# SpiSlvWiring.net
KiCad netlist of a schematic drawn in EAGLE
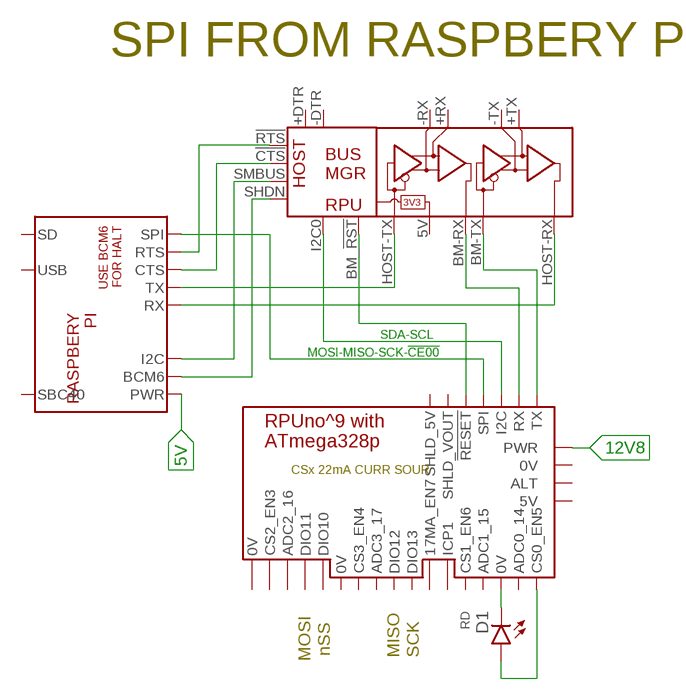
[diagram p0: schematic, sheet 1]

(export (version "E")
  (design (tool "Eeschema 10.0.6"))
  (components
    (comp (ref "BM1")
      (value "RPUNO")
      (footprint "eagle-import:NA-30")
      (libsource (lib "eagle-import") (part "RPUNO"))
    )
    (comp (ref "D1")
      (value "RD")
      (footprint "eagle-import:LED5MM")
      (libsource (lib "eagle-import") (part "LED5MM"))
    )
    (comp (ref "U$1")
      (value "PI")
      (footprint "eagle-import:NA-30")
      (libsource (lib "eagle-import") (part "PI"))
    )
    (comp (ref "U$2")
      (value "BUS_MGR")
      (footprint "eagle-import:WITH_RPU_NAMES")
      (libsource (lib "eagle-import") (part "BUS_MGR"))
    )
  )
  (nets
    (net (code "1") (name "/MOSI-MISO-SCK-~{CE00}") (class "Default")
      (node (ref "BM1") (pin "4") (pinfunction "SPI_4") (pintype "bidirectional"))
      (node (ref "U$1") (pin "10") (pinfunction "SPI_10") (pintype "bidirectional"))
    )
    (net (code "2") (name "/SDA-SCL") (class "Default")
      (node (ref "BM1") (pin "3") (pinfunction "I2C_3") (pintype "bidirectional"))
      (node (ref "U$2") (pin "I2C0") (pinfunction "I2C0_I2C0") (pintype "bidirectional"))
    )
    (net (code "3") (name "5V") (class "Default")
      (node (ref "U$1") (pin "12") (pinfunction "PWR_12") (pintype "bidirectional"))
    )
    (net (code "4") (name "12V8") (class "Default")
      (node (ref "BM1") (pin "8") (pinfunction "PWR_8") (pintype "bidirectional"))
    )
    (net (code "5") (name "Net-(BM1-0V-Pad26)") (class "Default")
      (node (ref "BM1") (pin "26") (pinfunction "0V_26") (pintype "bidirectional"))
      (node (ref "D1") (pin "K") (pinfunction "K_K") (pintype "passive"))
    )
    (net (code "6") (name "Net-(BM1-CS0_EN5)") (class "Default")
      (node (ref "BM1") (pin "23") (pinfunction "CS0_EN5_23") (pintype "bidirectional"))
      (node (ref "D1") (pin "A") (pinfunction "A_A") (pintype "passive"))
    )
    (net (code "7") (name "Net-(BM1-RX)") (class "Default")
      (node (ref "BM1") (pin "2") (pinfunction "RX_2") (pintype "bidirectional"))
      (node (ref "U$2") (pin "BM-RX") (pinfunction "BM_RX_BM-RX") (pintype "bidirectional"))
    )
    (net (code "8") (name "Net-(BM1-TX)") (class "Default")
      (node (ref "BM1") (pin "1") (pinfunction "TX_1") (pintype "bidirectional"))
      (node (ref "U$2") (pin "BM-TX") (pinfunction "BM_TX_BM-TX") (pintype "bidirectional"))
    )
    (net (code "9") (name "Net-(BM1-~{RESET})") (class "Default")
      (node (ref "BM1") (pin "5") (pinfunction "~{RESET}_5") (pintype "bidirectional"))
      (node (ref "U$2") (pin "BM_!RST!") (pinfunction "BM-~{RST}_BM_!RST!") (pintype "bidirectional"))
    )
    (net (code "10") (name "Net-(U$1-BCM6)") (class "Default")
      (node (ref "U$1") (pin "7") (pinfunction "BCM6_7") (pintype "bidirectional"))
      (node (ref "U$2") (pin "SHDN") (pinfunction "SHDN_SHDN") (pintype "bidirectional"))
    )
    (net (code "11") (name "Net-(U$1-CTS)") (class "Default")
      (node (ref "U$1") (pin "1") (pinfunction "CTS_1") (pintype "input"))
      (node (ref "U$2") (pin "!CTS") (pinfunction "~{CTS}_!CTS") (pintype "bidirectional"))
    )
    (net (code "12") (name "Net-(U$1-I2C)") (class "Default")
      (node (ref "U$1") (pin "8") (pinfunction "I2C_8") (pintype "bidirectional"))
      (node (ref "U$2") (pin "SMBUS") (pinfunction "SMBUS_SMBUS") (pintype "bidirectional"))
    )
    (net (code "13") (name "Net-(U$1-RTS)") (class "Default")
      (node (ref "U$1") (pin "2") (pinfunction "RTS_2") (pintype "input"))
      (node (ref "U$2") (pin "!RTS") (pinfunction "~{RTS}_!RTS") (pintype "bidirectional"))
    )
    (net (code "14") (name "Net-(U$1-RX)") (class "Default")
      (node (ref "U$1") (pin "3") (pinfunction "RX_3") (pintype "bidirectional"))
      (node (ref "U$2") (pin "HOST-RX") (pinfunction "HOST_RX_HOST-RX") (pintype "bidirectional"))
    )
    (net (code "15") (name "Net-(U$1-TX)") (class "Default")
      (node (ref "U$1") (pin "4") (pinfunction "TX_4") (pintype "bidirectional"))
      (node (ref "U$2") (pin "HOST-TX") (pinfunction "HOST_TX_HOST-TX") (pintype "bidirectional"))
    )
    (net (code "16") (name "unconnected-(BM1-0V-Pad9)") (class "Default")
      (node (ref "BM1") (pin "9") (pinfunction "0V_9") (pintype "bidirectional"))
    )
    (net (code "17") (name "unconnected-(BM1-0V-Pad27)") (class "Default")
      (node (ref "BM1") (pin "27") (pinfunction "0V_27") (pintype "bidirectional"))
    )
    (net (code "18") (name "unconnected-(BM1-0V-Pad28)") (class "Default")
      (node (ref "BM1") (pin "28") (pinfunction "0V_28") (pintype "bidirectional"))
    )
    (net (code "19") (name "unconnected-(BM1-5V-Pad19)") (class "Default")
      (node (ref "BM1") (pin "19") (pinfunction "5V_19") (pintype "bidirectional"))
    )
    (net (code "20") (name "unconnected-(BM1-17MA_EN7-Pad21)") (class "Default")
      (node (ref "BM1") (pin "21") (pinfunction "17MA_EN7_21") (pintype "bidirectional"))
    )
    (net (code "21") (name "unconnected-(BM1-ADC0_14-Pad11)") (class "Default")
      (node (ref "BM1") (pin "11") (pinfunction "ADC0_14_11") (pintype "bidirectional"))
    )
    (net (code "22") (name "unconnected-(BM1-ADC1_15-Pad10)") (class "Default")
      (node (ref "BM1") (pin "10") (pinfunction "ADC1_15_10") (pintype "bidirectional"))
    )
    (net (code "23") (name "unconnected-(BM1-ADC2_16-Pad13)") (class "Default")
      (node (ref "BM1") (pin "13") (pinfunction "ADC2_16_13") (pintype "bidirectional"))
    )
    (net (code "24") (name "unconnected-(BM1-ADC3_17-Pad16)") (class "Default")
      (node (ref "BM1") (pin "16") (pinfunction "ADC3_17_16") (pintype "bidirectional"))
    )
    (net (code "25") (name "unconnected-(BM1-ALT-Pad20)") (class "Default")
      (node (ref "BM1") (pin "20") (pinfunction "ALT_20") (pintype "bidirectional"))
    )
    (net (code "26") (name "unconnected-(BM1-CS1_EN6-Pad22)") (class "Default")
      (node (ref "BM1") (pin "22") (pinfunction "CS1_EN6_22") (pintype "bidirectional"))
    )
    (net (code "27") (name "unconnected-(BM1-CS2_EN3-Pad24)") (class "Default")
      (node (ref "BM1") (pin "24") (pinfunction "CS2_EN3_24") (pintype "bidirectional"))
    )
    (net (code "28") (name "unconnected-(BM1-CS3_EN4-Pad29)") (class "Default")
      (node (ref "BM1") (pin "29") (pinfunction "CS3_EN4_29") (pintype "bidirectional"))
    )
    (net (code "29") (name "unconnected-(BM1-DIO10-Pad15)") (class "Default")
      (node (ref "BM1") (pin "15") (pinfunction "DIO10_15") (pintype "bidirectional"))
    )
    (net (code "30") (name "unconnected-(BM1-DIO11-Pad14)") (class "Default")
      (node (ref "BM1") (pin "14") (pinfunction "DIO11_14") (pintype "bidirectional"))
    )
    (net (code "31") (name "unconnected-(BM1-DIO12-Pad17)") (class "Default")
      (node (ref "BM1") (pin "17") (pinfunction "DIO12_17") (pintype "bidirectional"))
    )
    (net (code "32") (name "unconnected-(BM1-DIO13-Pad18)") (class "Default")
      (node (ref "BM1") (pin "18") (pinfunction "DIO13_18") (pintype "bidirectional"))
    )
    (net (code "33") (name "unconnected-(BM1-ICP1-Pad12)") (class "Default")
      (node (ref "BM1") (pin "12") (pinfunction "ICP1_12") (pintype "bidirectional"))
    )
    (net (code "34") (name "unconnected-(BM1-SHLD_5V-Pad6)") (class "Default")
      (node (ref "BM1") (pin "6") (pinfunction "SHLD_5V_6") (pintype "bidirectional"))
    )
    (net (code "35") (name "unconnected-(BM1-SHLD_VOUT-Pad7)") (class "Default")
      (node (ref "BM1") (pin "7") (pinfunction "SHLD_VOUT_7") (pintype "bidirectional"))
    )
    (net (code "36") (name "unconnected-(U$1-SBC40-Pad5)") (class "Default")
      (node (ref "U$1") (pin "5") (pinfunction "SBC40_5") (pintype "input"))
    )
    (net (code "37") (name "unconnected-(U$1-SD-Pad9)") (class "Default")
      (node (ref "U$1") (pin "9") (pinfunction "SD_9") (pintype "input"))
    )
    (net (code "38") (name "unconnected-(U$1-USB-Pad11)") (class "Default")
      (node (ref "U$1") (pin "11") (pinfunction "USB_11") (pintype "input"))
    )
    (net (code "39") (name "unconnected-(U$2-PWR-Pad5V)") (class "Default")
      (node (ref "U$2") (pin "5V") (pinfunction "PWR_5V") (pintype "bidirectional"))
    )
    (net (code "40") (name "unconnected-(U$2-Pad+DTR)") (class "Default")
      (node (ref "U$2") (pin "+DTR") (pinfunction "+DTR_+DTR") (pintype "bidirectional"))
    )
    (net (code "41") (name "unconnected-(U$2-Pad+RX)") (class "Default")
      (node (ref "U$2") (pin "+RX") (pinfunction "+RX_+RX") (pintype "bidirectional"))
    )
    (net (code "42") (name "unconnected-(U$2-Pad+TX)") (class "Default")
      (node (ref "U$2") (pin "+TX") (pinfunction "+TX_+TX") (pintype "bidirectional"))
    )
    (net (code "43") (name "unconnected-(U$2-Pad-DTR)") (class "Default")
      (node (ref "U$2") (pin "-DTR") (pinfunction "-DTR_-DTR") (pintype "bidirectional"))
    )
    (net (code "44") (name "unconnected-(U$2-Pad-RX)") (class "Default")
      (node (ref "U$2") (pin "-RX") (pinfunction "-RX_-RX") (pintype "bidirectional"))
    )
    (net (code "45") (name "unconnected-(U$2-Pad-TX)") (class "Default")
      (node (ref "U$2") (pin "-TX") (pinfunction "-TX_-TX") (pintype "bidirectional"))
    )
  )
)
